# ws2812_example.net
KiCad netlist of a schematic drawn in EAGLE
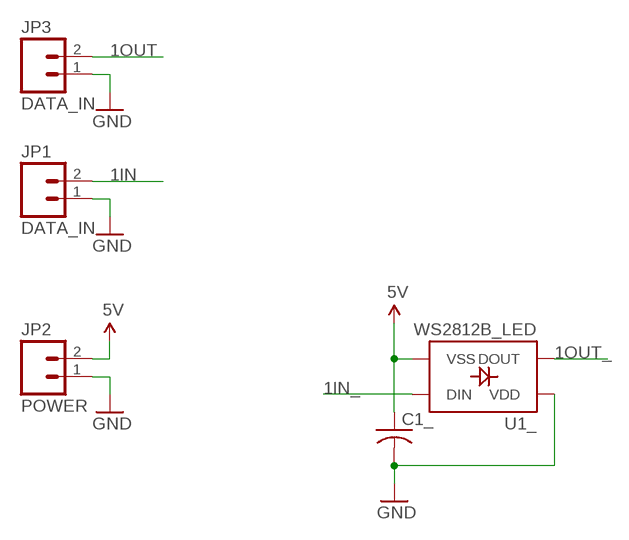
[diagram p0: schematic, sheet 1]

(export (version "E")
  (design (tool "Eeschema 10.0.6"))
  (components
    (comp (ref "C1_")
      (value "C-USC0603K")
      (footprint "eagle-import:C0603K")
      (libsource (lib "eagle-import") (part "C-USC0603K"))
    )
    (comp (ref "JP1")
      (value "DATA_IN")
      (footprint "eagle-import:SCREWTERMINAL-3.5MM-2_LOCK")
      (libsource (lib "eagle-import") (part "M023.5MM_LOCK"))
    )
    (comp (ref "JP2")
      (value "POWER")
      (footprint "eagle-import:SCREWTERMINAL-3.5MM-2_LOCK")
      (libsource (lib "eagle-import") (part "M023.5MM_LOCK"))
    )
    (comp (ref "JP3")
      (value "DATA_IN")
      (footprint "eagle-import:SCREWTERMINAL-3.5MM-2_LOCK")
      (libsource (lib "eagle-import") (part "M023.5MM_LOCK"))
    )
    (comp (ref "U1_")
      (value "WS2812B_LED")
      (footprint "eagle-import:WS2812B_LED")
      (libsource (lib "eagle-import") (part "WS2812B_LED"))
    )
  )
  (nets
    (net (code "1") (name "/1IN") (class "Default")
      (node (ref "JP1") (pin "2") (pinfunction "2_2") (pintype "passive"))
    )
    (net (code "2") (name "/1IN_") (class "Default")
      (node (ref "U1_") (pin "DIN") (pinfunction "DIN_DIN") (pintype "bidirectional"))
    )
    (net (code "3") (name "/1OUT") (class "Default")
      (node (ref "JP3") (pin "2") (pinfunction "2_2") (pintype "passive"))
    )
    (net (code "4") (name "/1OUT_") (class "Default")
      (node (ref "U1_") (pin "DOUT") (pinfunction "DOUT_DOUT") (pintype "bidirectional"))
    )
    (net (code "5") (name "5V") (class "Default")
      (node (ref "C1_") (pin "1") (pinfunction "1_1") (pintype "passive"))
      (node (ref "JP2") (pin "2") (pinfunction "2_2") (pintype "passive"))
      (node (ref "U1_") (pin "VSS") (pinfunction "VSS_VSS") (pintype "bidirectional"))
    )
    (net (code "6") (name "GND") (class "Default")
      (node (ref "C1_") (pin "2") (pinfunction "2_2") (pintype "passive"))
      (node (ref "JP1") (pin "1") (pinfunction "1_1") (pintype "passive"))
      (node (ref "JP2") (pin "1") (pinfunction "1_1") (pintype "passive"))
      (node (ref "JP3") (pin "1") (pinfunction "1_1") (pintype "passive"))
      (node (ref "U1_") (pin "VDD") (pinfunction "VDD_VDD") (pintype "bidirectional"))
    )
  )
)
